# DIGITAL_INPUT_2CH.net
KiCad netlist of a schematic drawn in Altium Designer
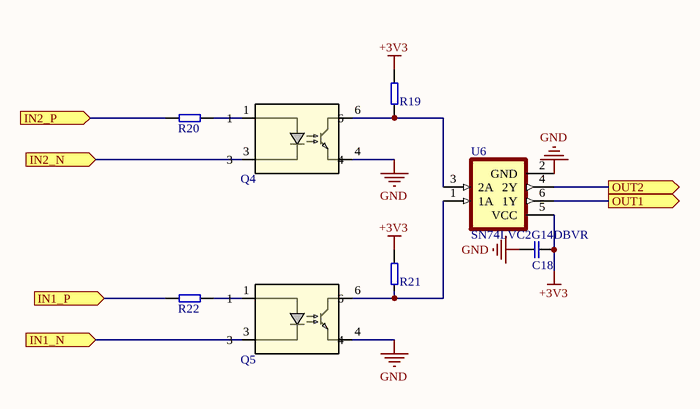
[diagram p0: DIGITAL_INPUT_2CH.SchDoc]

(export (version "E")
  (design (tool "Eeschema 10.0.6"))
  (components
    (comp (ref "C18")
      (value "0.1uF")
      (footprint "C0402")
      (description "CAP CER 0.1UF 25V X7R 0402")
      (fields (field (name "PART NUMBER") "04023C104KAT2A") (field (name "VOLTAGE") "25V"))
      (libsource (lib "anayurt") (part "CAP"))
    )
    (comp (ref "Q4")
      (value "TLP188(TPL,E")
      (footprint "OptoCoupler")
      (description "IC-188 OPTOISO 3.75KV TRANS SO6")
      (fields (field (name "COPYRIGHT") "Copyright (C) 2023 Ultra Librarian. All rights reserved."))
      (libsource (lib "anayurt") (part "OptoCoupler"))
    )
    (comp (ref "Q5")
      (value "TLP188(TPL,E(TPL,E")
      (footprint "OptoCoupler")
      (description "IC-188 OPTOISO 3.75KV TRANS SO6")
      (fields
        (field (name "MANUFACTURER_PART_NUMBER") "TLP188(TPL,E")
        (field (name "COPYRIGHT") "Copyright (C) 2023 Ultra Librarian. All rights reserved.")
      )
      (libsource (lib "anayurt") (part "OptoCoupler"))
    )
    (comp (ref "R19")
      (value "1K")
      (footprint "R0402")
      (description "RES SMD 1K OHM 0.1% 1/16W 0402")
      (fields (field (name "PART NUMBER") "RT0402BRE071KL") (field (name "TOLERANCE") "0.1%"))
      (libsource (lib "anayurt") (part "RES"))
    )
    (comp (ref "R20")
      (value "1K")
      (footprint "R0402")
      (description "RES SMD 1K OHM 0.1% 1/16W 0402")
      (fields (field (name "PART NUMBER") "RT0402BRE071KL") (field (name "TOLERANCE") "0.1%"))
      (libsource (lib "anayurt") (part "RES"))
    )
    (comp (ref "R21")
      (value "1K")
      (footprint "R0402")
      (description "RES SMD 1K OHM 0.1% 1/16W 0402")
      (fields (field (name "PART NUMBER") "RT0402BRE071KL") (field (name "TOLERANCE") "0.1%"))
      (libsource (lib "anayurt") (part "RES"))
    )
    (comp (ref "R22")
      (value "1K")
      (footprint "R0402")
      (description "RES SMD 1K OHM 0.1% 1/16W 0402")
      (fields (field (name "PART NUMBER") "RT0402BRE071KL") (field (name "TOLERANCE") "0.1%"))
      (libsource (lib "anayurt") (part "RES"))
    )
    (comp (ref "U6")
      (value "SN74LVC2G14DBVR")
      (footprint "SOT95P280X145-6N")
      (description "Dual Schmitt-Trigger Inverter 6-SOT-23 -40 to 125")
      (fields (field (name "MF") "Texas Instruments"))
      (libsource (lib "SN74LVC2G14DBVR") (part "SN74LVC2G14DBVR"))
    )
  )
  (nets
    (net (code "1") (name "+3V3") (class "Default")
      (node (ref "C18") (pin "2") (pinfunction "2_2") (pintype "passive"))
      (node (ref "R19") (pin "2") (pinfunction "2_2") (pintype "passive"))
      (node (ref "R21") (pin "2") (pinfunction "2_2") (pintype "passive"))
      (node (ref "U6") (pin "5") (pinfunction "VCC_5") (pintype "power_in"))
    )
    (net (code "2") (name "/IN1_N") (class "Default")
      (node (ref "Q5") (pin "3") (pinfunction "3_3") (pintype "passive"))
    )
    (net (code "3") (name "/IN1_P") (class "Default")
      (node (ref "R22") (pin "2") (pinfunction "2_2") (pintype "passive"))
    )
    (net (code "4") (name "/IN2_N") (class "Default")
      (node (ref "Q4") (pin "3") (pinfunction "3_3") (pintype "passive"))
    )
    (net (code "5") (name "/IN2_P") (class "Default")
      (node (ref "R20") (pin "2") (pinfunction "2_2") (pintype "passive"))
    )
    (net (code "6") (name "/OUT1") (class "Default")
      (node (ref "U6") (pin "6") (pinfunction "1Y_6") (pintype "output"))
    )
    (net (code "7") (name "/OUT2") (class "Default")
      (node (ref "U6") (pin "4") (pinfunction "2Y_4") (pintype "output"))
    )
    (net (code "8") (name "GND") (class "Default")
      (node (ref "C18") (pin "1") (pinfunction "1_1") (pintype "passive"))
      (node (ref "Q4") (pin "4") (pinfunction "4_4") (pintype "passive"))
      (node (ref "Q5") (pin "4") (pinfunction "4_4") (pintype "passive"))
      (node (ref "U6") (pin "2") (pinfunction "GND_2") (pintype "power_in"))
    )
    (net (code "9") (name "Net-(Q4-Pad1)") (class "Default")
      (node (ref "Q4") (pin "1") (pinfunction "1_1") (pintype "passive"))
      (node (ref "R20") (pin "1") (pinfunction "1_1") (pintype "passive"))
    )
    (net (code "10") (name "Net-(Q5-Pad1)") (class "Default")
      (node (ref "Q5") (pin "1") (pinfunction "1_1") (pintype "passive"))
      (node (ref "R22") (pin "1") (pinfunction "1_1") (pintype "passive"))
    )
    (net (code "11") (name "Net-(U6-1A)") (class "Default")
      (node (ref "Q5") (pin "6") (pinfunction "6_6") (pintype "passive"))
      (node (ref "R21") (pin "1") (pinfunction "1_1") (pintype "passive"))
      (node (ref "U6") (pin "1") (pinfunction "1A_1") (pintype "input"))
    )
    (net (code "12") (name "Net-(U6-2A)") (class "Default")
      (node (ref "Q4") (pin "6") (pinfunction "6_6") (pintype "passive"))
      (node (ref "R19") (pin "1") (pinfunction "1_1") (pintype "passive"))
      (node (ref "U6") (pin "3") (pinfunction "2A_3") (pintype "input"))
    )
  )
)
